# untitled.net
KiCad netlist of a schematic drawn in EAGLE
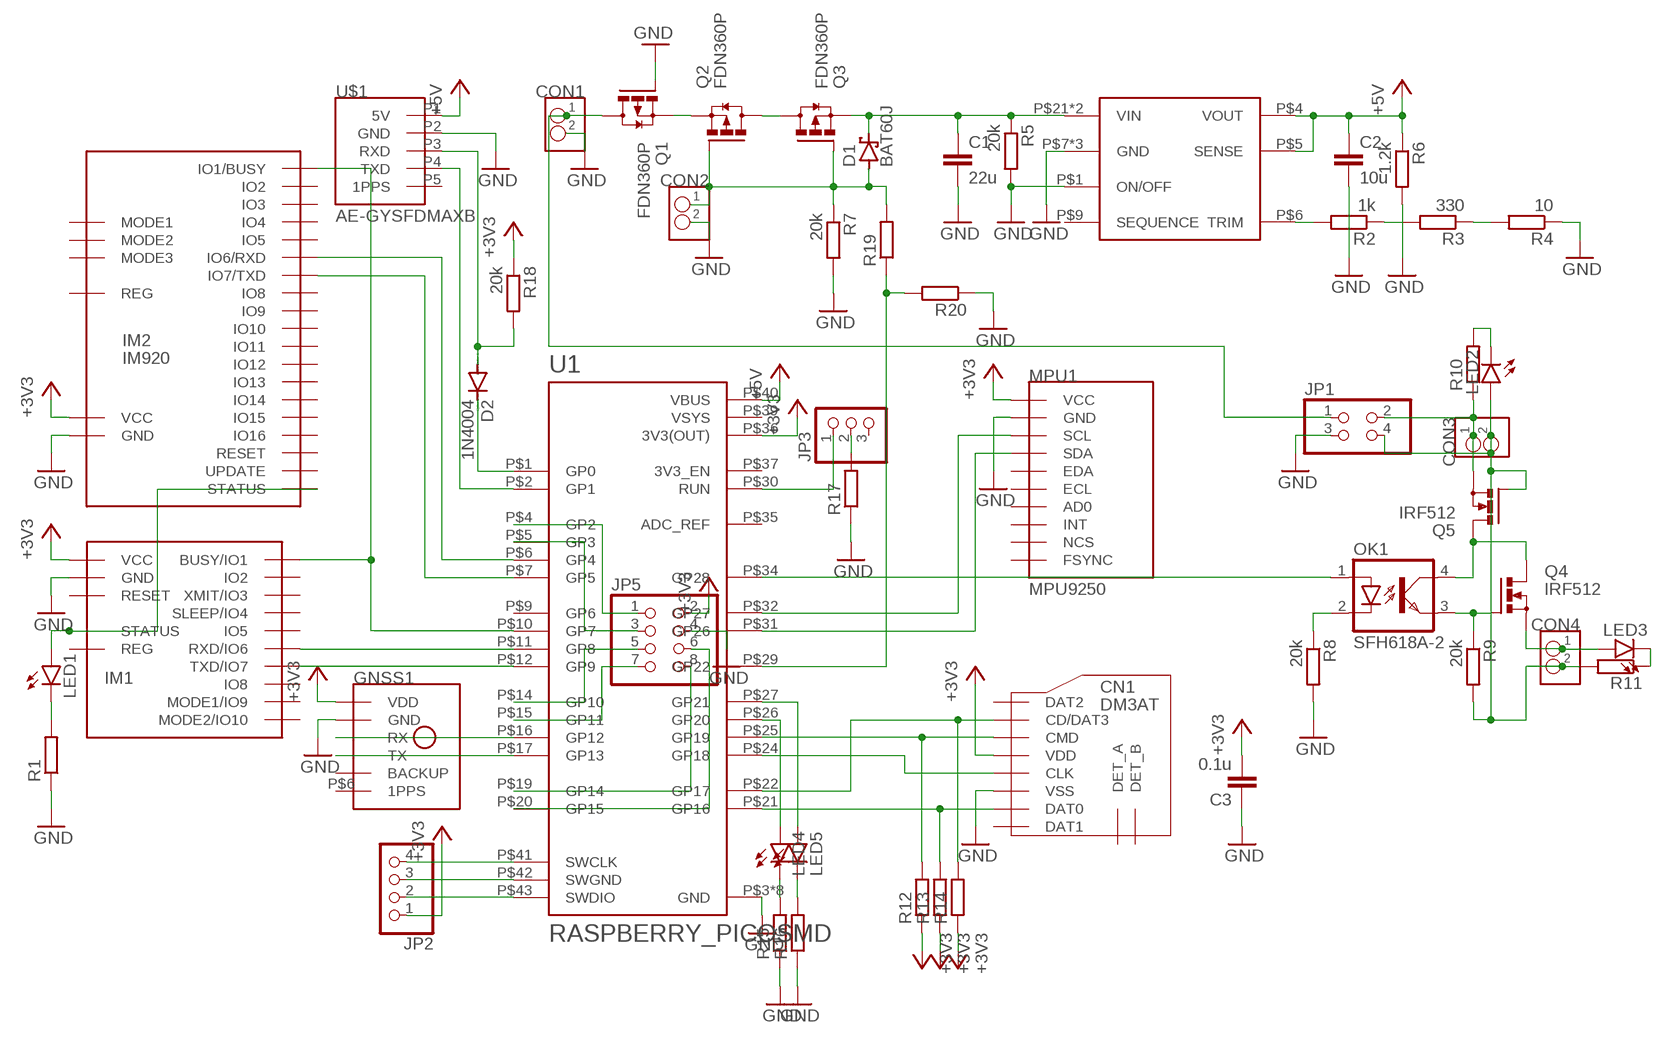
[diagram p0: schematic, sheet 1]

(export (version "E")
  (design (tool "Eeschema 10.0.6"))
  (components
    (comp (ref "C1")
      (value "22u")
      (footprint "eagle-import:C0805")
      (libsource (lib "eagle-import") (part "C-EUC0805"))
    )
    (comp (ref "C2")
      (value "10u")
      (footprint "eagle-import:C0805")
      (libsource (lib "eagle-import") (part "C-EUC0805"))
    )
    (comp (ref "C3")
      (value "0.1u")
      (footprint "eagle-import:C0805")
      (libsource (lib "eagle-import") (part "C-EUC0805"))
    )
    (comp (ref "CN1")
      (value "DM3AT")
      (footprint "eagle-import:DM3AT")
      (libsource (lib "eagle-import") (part "DM3AT"))
    )
    (comp (ref "CON1")
      (value "B2B-XH-A")
      (footprint "eagle-import:B2B-XH-A")
      (libsource (lib "eagle-import") (part "B2B-XH-A"))
    )
    (comp (ref "CON2")
      (value "B2B-XH-A")
      (footprint "eagle-import:B2B-XH-A")
      (libsource (lib "eagle-import") (part "B2B-XH-A"))
    )
    (comp (ref "CON3")
      (value "B2B-XH-A")
      (footprint "eagle-import:B2B-XH-A")
      (libsource (lib "eagle-import") (part "B2B-XH-A"))
    )
    (comp (ref "CON4")
      (value "B2B-XH-A")
      (footprint "eagle-import:B2B-XH-A")
      (libsource (lib "eagle-import") (part "B2B-XH-A"))
    )
    (comp (ref "D1")
      (value "BAT60J")
      (footprint "eagle-import:SOD323_ST")
      (libsource (lib "eagle-import") (part "BAT60J"))
    )
    (comp (ref "D2")
      (value "1N4004")
      (footprint "eagle-import:DO41-10")
      (libsource (lib "eagle-import") (part "1N4004"))
    )
    (comp (ref "GNSS1")
      (value "GYSFDMAXB")
      (footprint "eagle-import:GYSFDMAXB")
      (libsource (lib "eagle-import") (part "GYSFDMAXB"))
    )
    (comp (ref "I1")
      (value "ＯＫＬ-Ｔ/３-Ｗ５Ｎ-Ｃ")
      (footprint "eagle-import:ＯＫＬ-Ｔ_３-Ｗ５Ｎ-Ｃ")
      (libsource (lib "eagle-import") (part "ＯＫＬ-Ｔ/３-Ｗ５Ｎ-Ｃ"))
    )
    (comp (ref "IM1")
      (value "IM920C")
      (footprint "eagle-import:IM920C")
      (libsource (lib "eagle-import") (part "IM920C"))
    )
    (comp (ref "IM2")
      (value "IM920")
      (footprint "eagle-import:IM920")
      (libsource (lib "eagle-import") (part "IM920"))
    )
    (comp (ref "JP1")
      (value "PINHD-2X2")
      (footprint "eagle-import:2X02")
      (libsource (lib "eagle-import") (part "PINHD-2X2"))
    )
    (comp (ref "JP2")
      (value "PINHD-1X4")
      (footprint "eagle-import:1X04")
      (libsource (lib "eagle-import") (part "PINHD-1X4"))
    )
    (comp (ref "JP3")
      (value "PINHD-1X3")
      (footprint "eagle-import:1X03")
      (libsource (lib "eagle-import") (part "PINHD-1X3"))
    )
    (comp (ref "JP5")
      (value "PINHD-2X4")
      (footprint "eagle-import:2X04")
      (libsource (lib "eagle-import") (part "PINHD-2X4"))
    )
    (comp (ref "LED1")
      (value "LEDCHIP-LED0805")
      (footprint "eagle-import:CHIP-LED0805")
      (libsource (lib "eagle-import") (part "LEDCHIP-LED0805"))
    )
    (comp (ref "LED2")
      (value "LEDCHIP-LED0805")
      (footprint "eagle-import:CHIP-LED0805")
      (libsource (lib "eagle-import") (part "LEDCHIP-LED0805"))
    )
    (comp (ref "LED3")
      (value "LEDCHIP-LED0805")
      (footprint "eagle-import:CHIP-LED0805")
      (libsource (lib "eagle-import") (part "LEDCHIP-LED0805"))
    )
    (comp (ref "LED4")
      (value "LEDCHIP-LED0805")
      (footprint "eagle-import:CHIP-LED0805")
      (libsource (lib "eagle-import") (part "LEDCHIP-LED0805"))
    )
    (comp (ref "LED5")
      (value "LEDCHIP-LED0805")
      (footprint "eagle-import:CHIP-LED0805")
      (libsource (lib "eagle-import") (part "LEDCHIP-LED0805"))
    )
    (comp (ref "MPU1")
      (value "MPU9250")
      (footprint "eagle-import:GY-9250")
      (libsource (lib "eagle-import") (part "MPU9250"))
    )
    (comp (ref "OK1")
      (value "SFH618A-2")
      (footprint "eagle-import:DIP4")
      (fields (field (name "MF") "VISHAY/TELEFUNKEN"))
      (libsource (lib "eagle-import") (part "SFH618?A-2"))
    )
    (comp (ref "Q1")
      (value "FDN360P")
      (footprint "eagle-import:SUPER-SOT3")
      (libsource (lib "eagle-import") (part "FDN360P"))
    )
    (comp (ref "Q2")
      (value "FDN360P")
      (footprint "eagle-import:SUPER-SOT3")
      (libsource (lib "eagle-import") (part "FDN360P"))
    )
    (comp (ref "Q3")
      (value "FDN360P")
      (footprint "eagle-import:SUPER-SOT3")
      (libsource (lib "eagle-import") (part "FDN360P"))
    )
    (comp (ref "Q4")
      (value "IRF512")
      (footprint "eagle-import:TO220BV")
      (libsource (lib "eagle-import") (part "IRF512"))
    )
    (comp (ref "Q5")
      (value "IRF512")
      (footprint "eagle-import:TO220BV")
      (libsource (lib "eagle-import") (part "IRF512"))
    )
    (comp (ref "R1")
      (value "R-EU_R0603")
      (footprint "eagle-import:R0603")
      (libsource (lib "eagle-import") (part "R-EU_R0603"))
    )
    (comp (ref "R2")
      (value "1k")
      (footprint "eagle-import:R0603")
      (libsource (lib "eagle-import") (part "R-EU_R0603"))
    )
    (comp (ref "R3")
      (value "330")
      (footprint "eagle-import:R0603")
      (libsource (lib "eagle-import") (part "R-EU_R0603"))
    )
    (comp (ref "R4")
      (value "10")
      (footprint "eagle-import:R0603")
      (libsource (lib "eagle-import") (part "R-EU_R0603"))
    )
    (comp (ref "R5")
      (value "20k")
      (footprint "eagle-import:R0603")
      (libsource (lib "eagle-import") (part "R-EU_R0603"))
    )
    (comp (ref "R6")
      (value "1.2k")
      (footprint "eagle-import:R0603")
      (libsource (lib "eagle-import") (part "R-EU_R0603"))
    )
    (comp (ref "R7")
      (value "20k")
      (footprint "eagle-import:R0603")
      (libsource (lib "eagle-import") (part "R-EU_R0603"))
    )
    (comp (ref "R8")
      (value "20k")
      (footprint "eagle-import:R0603")
      (libsource (lib "eagle-import") (part "R-EU_R0603"))
    )
    (comp (ref "R9")
      (value "20k")
      (footprint "eagle-import:R0603")
      (libsource (lib "eagle-import") (part "R-EU_R0603"))
    )
    (comp (ref "R10")
      (value "R-EU_R0603")
      (footprint "eagle-import:R0603")
      (libsource (lib "eagle-import") (part "R-EU_R0603"))
    )
    (comp (ref "R11")
      (value "R-EU_R0603")
      (footprint "eagle-import:R0603")
      (libsource (lib "eagle-import") (part "R-EU_R0603"))
    )
    (comp (ref "R12")
      (value "R-EU_R0603")
      (footprint "eagle-import:R0603")
      (libsource (lib "eagle-import") (part "R-EU_R0603"))
    )
    (comp (ref "R13")
      (value "R-EU_R0603")
      (footprint "eagle-import:R0603")
      (libsource (lib "eagle-import") (part "R-EU_R0603"))
    )
    (comp (ref "R14")
      (value "R-EU_R0603")
      (footprint "eagle-import:R0603")
      (libsource (lib "eagle-import") (part "R-EU_R0603"))
    )
    (comp (ref "R15")
      (value "R-EU_R0603")
      (footprint "eagle-import:R0603")
      (libsource (lib "eagle-import") (part "R-EU_R0603"))
    )
    (comp (ref "R16")
      (value "R-EU_R0603")
      (footprint "eagle-import:R0603")
      (libsource (lib "eagle-import") (part "R-EU_R0603"))
    )
    (comp (ref "R17")
      (value "R-EU_R0603")
      (footprint "eagle-import:R0603")
      (libsource (lib "eagle-import") (part "R-EU_R0603"))
    )
    (comp (ref "R18")
      (value "20k")
      (footprint "eagle-import:R0603")
      (libsource (lib "eagle-import") (part "R-EU_R0603"))
    )
    (comp (ref "R19")
      (value "R-EU_R0603")
      (footprint "eagle-import:R0603")
      (libsource (lib "eagle-import") (part "R-EU_R0603"))
    )
    (comp (ref "R20")
      (value "R-EU_R0603")
      (footprint "eagle-import:R0603")
      (libsource (lib "eagle-import") (part "R-EU_R0603"))
    )
    (comp (ref "U$1")
      (value "AE-GYSFDMAXB")
      (footprint "eagle-import:AE-GYSFDMAXB")
      (libsource (lib "eagle-import") (part "AE-GYSFDMAXB"))
    )
    (comp (ref "U1")
      (value "RASPBERRY_PICOSMD")
      (footprint "eagle-import:PICO-PKG-SMD")
      (libsource (lib "eagle-import") (part "RASPBERRY_PICOSMD"))
    )
  )
  (nets
    (net (code "1") (name "+3V3") (class "Default")
      (node (ref "C3") (pin "2") (pinfunction "2_2") (pintype "passive"))
      (node (ref "CN1") (pin "VDD") (pinfunction "VDD_VDD") (pintype "bidirectional"))
      (node (ref "GNSS1") (pin "P$16") (pinfunction "VDD_P$16") (pintype "bidirectional"))
      (node (ref "IM1") (pin "$P17") (pinfunction "VCC_$P17") (pintype "bidirectional"))
      (node (ref "IM2") (pin "IO23") (pinfunction "VCC_IO23") (pintype "bidirectional"))
      (node (ref "JP2") (pin "1") (pinfunction "1_1") (pintype "passive"))
      (node (ref "JP5") (pin "2") (pinfunction "2_2") (pintype "passive"))
      (node (ref "MPU1") (pin "P1") (pinfunction "VCC_P1") (pintype "bidirectional"))
      (node (ref "R12") (pin "1") (pinfunction "1_1") (pintype "passive"))
      (node (ref "R13") (pin "1") (pinfunction "1_1") (pintype "passive"))
      (node (ref "R14") (pin "1") (pinfunction "1_1") (pintype "passive"))
      (node (ref "R18") (pin "1") (pinfunction "1_1") (pintype "passive"))
      (node (ref "U1") (pin "P$36") (pinfunction "3V3(OUT)_P$36") (pintype "power_in"))
    )
    (net (code "2") (name "+5V") (class "Default")
      (node (ref "C2") (pin "1") (pinfunction "1_1") (pintype "passive"))
      (node (ref "I1") (pin "P$4") (pinfunction "VOUT_P$4") (pintype "bidirectional"))
      (node (ref "I1") (pin "P$5") (pinfunction "SENSE_P$5") (pintype "bidirectional"))
      (node (ref "R6") (pin "1") (pinfunction "1_1") (pintype "passive"))
      (node (ref "U$1") (pin "P1") (pinfunction "5V_P1") (pintype "bidirectional"))
      (node (ref "U1") (pin "P$40") (pinfunction "VBUS_P$40") (pintype "power_in"))
    )
    (net (code "3") (name "/VSYS") (class "Default")
      (node (ref "U1") (pin "P$39") (pinfunction "VSYS_P$39") (pintype "power_in"))
    )
    (net (code "4") (name "GND") (class "Default")
      (node (ref "C1") (pin "2") (pinfunction "2_2") (pintype "passive"))
      (node (ref "C2") (pin "2") (pinfunction "2_2") (pintype "passive"))
      (node (ref "C3") (pin "1") (pinfunction "1_1") (pintype "passive"))
      (node (ref "CN1") (pin "VSS") (pinfunction "VSS_VSS") (pintype "bidirectional"))
      (node (ref "CON1") (pin "P$2") (pinfunction "2_P$2") (pintype "bidirectional"))
      (node (ref "CON2") (pin "P$2") (pinfunction "2_P$2") (pintype "bidirectional"))
      (node (ref "GNSS1") (pin "P$1") (pinfunction "GND_P$1") (pintype "bidirectional"))
      (node (ref "GNSS1") (pin "P$10") (pinfunction "GND_P$10") (pintype "bidirectional"))
      (node (ref "GNSS1") (pin "P$12") (pinfunction "GND_P$12") (pintype "bidirectional"))
      (node (ref "GNSS1") (pin "P$19") (pinfunction "GND_P$19") (pintype "bidirectional"))
      (node (ref "GNSS1") (pin "P$2") (pinfunction "GND_P$2") (pintype "bidirectional"))
      (node (ref "GNSS1") (pin "P$20") (pinfunction "GND_P$20") (pintype "bidirectional"))
      (node (ref "GNSS1") (pin "P$7") (pinfunction "GND_P$7") (pintype "bidirectional"))
      (node (ref "I1") (pin "P$1") (pinfunction "ON/OFF_P$1") (pintype "bidirectional"))
      (node (ref "I1") (pin "P$31") (pinfunction "GND_P$31") (pintype "bidirectional"))
      (node (ref "I1") (pin "P$32") (pinfunction "GND_P$32") (pintype "bidirectional"))
      (node (ref "I1") (pin "P$7") (pinfunction "GND_P$7") (pintype "bidirectional"))
      (node (ref "IM1") (pin "$P18") (pinfunction "GND_$P18") (pintype "bidirectional"))
      (node (ref "IM2") (pin "IO24") (pinfunction "GND_IO24") (pintype "bidirectional"))
      (node (ref "JP1") (pin "3") (pinfunction "3_3") (pintype "passive"))
      (node (ref "JP5") (pin "4") (pinfunction "4_4") (pintype "passive"))
      (node (ref "MPU1") (pin "P2") (pinfunction "GND_P2") (pintype "bidirectional"))
      (node (ref "Q1") (pin "1") (pinfunction "G_1") (pintype "passive"))
      (node (ref "R1") (pin "1") (pinfunction "1_1") (pintype "passive"))
      (node (ref "R15") (pin "1") (pinfunction "1_1") (pintype "passive"))
      (node (ref "R16") (pin "1") (pinfunction "1_1") (pintype "passive"))
      (node (ref "R17") (pin "1") (pinfunction "1_1") (pintype "passive"))
      (node (ref "R20") (pin "1") (pinfunction "1_1") (pintype "passive"))
      (node (ref "R4") (pin "1") (pinfunction "1_1") (pintype "passive"))
      (node (ref "R5") (pin "2") (pinfunction "2_2") (pintype "passive"))
      (node (ref "R6") (pin "2") (pinfunction "2_2") (pintype "passive"))
      (node (ref "R7") (pin "2") (pinfunction "2_2") (pintype "passive"))
      (node (ref "R8") (pin "2") (pinfunction "2_2") (pintype "passive"))
      (node (ref "U$1") (pin "P2") (pinfunction "GND_P2") (pintype "bidirectional"))
      (node (ref "U1") (pin "P$13") (pinfunction "GND_P$13") (pintype "power_in"))
      (node (ref "U1") (pin "P$18") (pinfunction "GND_P$18") (pintype "power_in"))
      (node (ref "U1") (pin "P$23") (pinfunction "GND_P$23") (pintype "power_in"))
      (node (ref "U1") (pin "P$28") (pinfunction "GND_P$28") (pintype "power_in"))
      (node (ref "U1") (pin "P$3") (pinfunction "GND_P$3") (pintype "power_in"))
      (node (ref "U1") (pin "P$33") (pinfunction "GND_P$33") (pintype "power_in"))
      (node (ref "U1") (pin "P$38") (pinfunction "GND_P$38") (pintype "power_in"))
      (node (ref "U1") (pin "P$8") (pinfunction "GND_P$8") (pintype "power_in"))
    )
    (net (code "5") (name "Net-(CON1-1)") (class "Default")
      (node (ref "CON1") (pin "P$1") (pinfunction "1_P$1") (pintype "bidirectional"))
      (node (ref "JP1") (pin "1") (pinfunction "1_1") (pintype "passive"))
      (node (ref "Q1") (pin "3") (pinfunction "D_3") (pintype "passive"))
    )
    (net (code "6") (name "Net-(CON2-1)") (class "Default")
      (node (ref "CON2") (pin "P$1") (pinfunction "1_P$1") (pintype "bidirectional"))
      (node (ref "D1") (pin "A") (pinfunction "A_A") (pintype "passive"))
      (node (ref "Q2") (pin "1") (pinfunction "G_1") (pintype "passive"))
      (node (ref "Q3") (pin "1") (pinfunction "G_1") (pintype "passive"))
      (node (ref "R19") (pin "2") (pinfunction "2_2") (pintype "passive"))
      (node (ref "R7") (pin "1") (pinfunction "1_1") (pintype "passive"))
    )
    (net (code "7") (name "Net-(CON3-1)") (class "Default")
      (node (ref "CON3") (pin "P$1") (pinfunction "1_P$1") (pintype "bidirectional"))
      (node (ref "JP1") (pin "2") (pinfunction "2_2") (pintype "passive"))
      (node (ref "Q5") (pin "S") (pinfunction "S_S") (pintype "passive"))
      (node (ref "R10") (pin "1") (pinfunction "1_1") (pintype "passive"))
    )
    (net (code "8") (name "Net-(CON3-2)") (class "Default")
      (node (ref "CON3") (pin "P$2") (pinfunction "2_P$2") (pintype "bidirectional"))
      (node (ref "CON4") (pin "P$2") (pinfunction "2_P$2") (pintype "bidirectional"))
      (node (ref "JP1") (pin "4") (pinfunction "4_4") (pintype "passive"))
      (node (ref "LED2") (pin "A") (pinfunction "A_A") (pintype "passive"))
      (node (ref "Q5") (pin "G") (pinfunction "G_G") (pintype "passive"))
      (node (ref "R11") (pin "2") (pinfunction "2_2") (pintype "passive"))
      (node (ref "R9") (pin "2") (pinfunction "2_2") (pintype "passive"))
    )
    (net (code "9") (name "Net-(CON4-1)") (class "Default")
      (node (ref "CON4") (pin "P$1") (pinfunction "1_P$1") (pintype "bidirectional"))
      (node (ref "LED3") (pin "A") (pinfunction "A_A") (pintype "passive"))
      (node (ref "Q4") (pin "S") (pinfunction "S_S") (pintype "passive"))
    )
    (net (code "10") (name "Net-(GNSS1-RX)") (class "Default")
      (node (ref "GNSS1") (pin "P$3") (pinfunction "RX_P$3") (pintype "bidirectional"))
      (node (ref "U1") (pin "P$16") (pinfunction "GP12_P$16") (pintype "bidirectional"))
    )
    (net (code "11") (name "Net-(GNSS1-TX)") (class "Default")
      (node (ref "GNSS1") (pin "P$5") (pinfunction "TX_P$5") (pintype "bidirectional"))
      (node (ref "U1") (pin "P$17") (pinfunction "GP13_P$17") (pintype "bidirectional"))
    )
    (net (code "12") (name "Net-(I1-TRIM)") (class "Default")
      (node (ref "I1") (pin "P$6") (pinfunction "TRIM_P$6") (pintype "bidirectional"))
      (node (ref "R2") (pin "2") (pinfunction "2_2") (pintype "passive"))
    )
    (net (code "13") (name "Net-(IM1-BUSY{slash}IO1)") (class "Default")
      (node (ref "IM1") (pin "$P1") (pinfunction "BUSY/IO1_$P1") (pintype "bidirectional"))
      (node (ref "IM2") (pin "IO1") (pinfunction "IO1/BUSY_IO1") (pintype "bidirectional"))
      (node (ref "U1") (pin "P$10") (pinfunction "GP7_P$10") (pintype "bidirectional"))
    )
    (net (code "14") (name "Net-(IM1-RXD{slash}IO6)") (class "Default")
      (node (ref "IM1") (pin "$P6") (pinfunction "RXD/IO6_$P6") (pintype "bidirectional"))
      (node (ref "U1") (pin "P$11") (pinfunction "GP8_P$11") (pintype "bidirectional"))
    )
    (net (code "15") (name "Net-(IM1-STATUS)") (class "Default")
      (node (ref "IM1") (pin "$P15") (pinfunction "STATUS_$P15") (pintype "bidirectional"))
      (node (ref "IM2") (pin "IO21") (pinfunction "STATUS_IO21") (pintype "bidirectional"))
      (node (ref "LED1") (pin "A") (pinfunction "A_A") (pintype "passive"))
    )
    (net (code "16") (name "Net-(IM1-TXD{slash}IO7)") (class "Default")
      (node (ref "IM1") (pin "$P7") (pinfunction "TXD/IO7_$P7") (pintype "bidirectional"))
      (node (ref "U1") (pin "P$12") (pinfunction "GP9_P$12") (pintype "bidirectional"))
    )
    (net (code "17") (name "Net-(IM2-IO6{slash}RXD)") (class "Default")
      (node (ref "IM2") (pin "IO6") (pinfunction "IO6/RXD_IO6") (pintype "bidirectional"))
      (node (ref "U1") (pin "P$6") (pinfunction "GP4_P$6") (pintype "bidirectional"))
    )
    (net (code "18") (name "Net-(IM2-IO7{slash}TXD)") (class "Default")
      (node (ref "IM2") (pin "IO7") (pinfunction "IO7/TXD_IO7") (pintype "bidirectional"))
      (node (ref "U1") (pin "P$7") (pinfunction "GP5_P$7") (pintype "bidirectional"))
    )
    (net (code "19") (name "Net-(JP3-Pad2)") (class "Default")
      (node (ref "JP3") (pin "2") (pinfunction "2_2") (pintype "passive"))
      (node (ref "R17") (pin "2") (pinfunction "2_2") (pintype "passive"))
    )
    (net (code "20") (name "Net-(LED1-PadC)") (class "Default")
      (node (ref "LED1") (pin "C") (pinfunction "C_C") (pintype "passive"))
      (node (ref "R1") (pin "2") (pinfunction "2_2") (pintype "passive"))
    )
    (net (code "21") (name "Net-(LED2-PadC)") (class "Default")
      (node (ref "LED2") (pin "C") (pinfunction "C_C") (pintype "passive"))
      (node (ref "R10") (pin "2") (pinfunction "2_2") (pintype "passive"))
    )
    (net (code "22") (name "Net-(LED3-PadC)") (class "Default")
      (node (ref "LED3") (pin "C") (pinfunction "C_C") (pintype "passive"))
      (node (ref "R11") (pin "1") (pinfunction "1_1") (pintype "passive"))
    )
    (net (code "23") (name "Net-(LED4-PadC)") (class "Default")
      (node (ref "LED4") (pin "C") (pinfunction "C_C") (pintype "passive"))
      (node (ref "R15") (pin "2") (pinfunction "2_2") (pintype "passive"))
    )
    (net (code "24") (name "Net-(LED5-PadC)") (class "Default")
      (node (ref "LED5") (pin "C") (pinfunction "C_C") (pintype "passive"))
      (node (ref "R16") (pin "2") (pinfunction "2_2") (pintype "passive"))
    )
    (net (code "25") (name "Net-(MPU1-SCL)") (class "Default")
      (node (ref "MPU1") (pin "P3") (pinfunction "SCL_P3") (pintype "bidirectional"))
      (node (ref "U1") (pin "P$32") (pinfunction "GP27_P$32") (pintype "bidirectional"))
    )
    (net (code "26") (name "Net-(MPU1-SDA)") (class "Default")
      (node (ref "MPU1") (pin "P4") (pinfunction "SDA_P4") (pintype "bidirectional"))
      (node (ref "U1") (pin "P$31") (pinfunction "GP26_P$31") (pintype "bidirectional"))
    )
    (net (code "27") (name "Net-(OK1-A)") (class "Default")
      (node (ref "OK1") (pin "1") (pinfunction "A_1") (pintype "passive"))
      (node (ref "U1") (pin "P$34") (pinfunction "GP28_P$34") (pintype "bidirectional"))
    )
    (net (code "28") (name "Net-(OK1-C)") (class "Default")
      (node (ref "OK1") (pin "2") (pinfunction "C_2") (pintype "passive"))
      (node (ref "R8") (pin "1") (pinfunction "1_1") (pintype "passive"))
    )
    (net (code "29") (name "Net-(OK1-COL)") (class "Default")
      (node (ref "OK1") (pin "4") (pinfunction "COL_4") (pintype "passive"))
      (node (ref "Q4") (pin "D") (pinfunction "D_D") (pintype "passive"))
      (node (ref "Q5") (pin "D") (pinfunction "D_D") (pintype "passive"))
    )
    (net (code "30") (name "Net-(OK1-EMIT)") (class "Default")
      (node (ref "OK1") (pin "3") (pinfunction "EMIT_3") (pintype "passive"))
      (node (ref "Q4") (pin "G") (pinfunction "G_G") (pintype "passive"))
      (node (ref "R9") (pin "1") (pinfunction "1_1") (pintype "passive"))
    )
    (net (code "31") (name "Net-(Q1-S)") (class "Default")
      (node (ref "Q1") (pin "2") (pinfunction "S_2") (pintype "passive"))
      (node (ref "Q2") (pin "2") (pinfunction "S_2") (pintype "passive"))
    )
    (net (code "32") (name "Net-(Q2-D)") (class "Default")
      (node (ref "Q2") (pin "3") (pinfunction "D_3") (pintype "passive"))
      (node (ref "Q3") (pin "3") (pinfunction "D_3") (pintype "passive"))
    )
    (net (code "33") (name "Net-(Q3-S)") (class "Default")
      (node (ref "C1") (pin "1") (pinfunction "1_1") (pintype "passive"))
      (node (ref "D1") (pin "C") (pinfunction "C_C") (pintype "passive"))
      (node (ref "I1") (pin "P$21") (pinfunction "VIN_P$21") (pintype "bidirectional"))
      (node (ref "I1") (pin "P$22") (pinfunction "VIN_P$22") (pintype "bidirectional"))
      (node (ref "Q3") (pin "2") (pinfunction "S_2") (pintype "passive"))
      (node (ref "R5") (pin "1") (pinfunction "1_1") (pintype "passive"))
    )
    (net (code "34") (name "Net-(R2-Pad1)") (class "Default")
      (node (ref "R2") (pin "1") (pinfunction "1_1") (pintype "passive"))
      (node (ref "R3") (pin "2") (pinfunction "2_2") (pintype "passive"))
    )
    (net (code "35") (name "Net-(R3-Pad1)") (class "Default")
      (node (ref "R3") (pin "1") (pinfunction "1_1") (pintype "passive"))
      (node (ref "R4") (pin "2") (pinfunction "2_2") (pintype "passive"))
    )
    (net (code "36") (name "Net-(U$1-RXD)") (class "Default")
      (node (ref "D2") (pin "A") (pinfunction "A_A") (pintype "passive"))
      (node (ref "R18") (pin "2") (pinfunction "2_2") (pintype "passive"))
      (node (ref "U$1") (pin "P3") (pinfunction "RXD_P3") (pintype "bidirectional"))
    )
    (net (code "37") (name "Net-(U$1-TXD)") (class "Default")
      (node (ref "U$1") (pin "P4") (pinfunction "TXD_P4") (pintype "bidirectional"))
      (node (ref "U1") (pin "P$2") (pinfunction "GP1_P$2") (pintype "bidirectional"))
    )
    (net (code "38") (name "Net-(U1-GP0)") (class "Default")
      (node (ref "D2") (pin "C") (pinfunction "C_C") (pintype "passive"))
      (node (ref "U1") (pin "P$1") (pinfunction "GP0_P$1") (pintype "bidirectional"))
    )
    (net (code "39") (name "Net-(U1-GP2)") (class "Default")
      (node (ref "JP5") (pin "1") (pinfunction "1_1") (pintype "passive"))
      (node (ref "U1") (pin "P$4") (pinfunction "GP2_P$4") (pintype "bidirectional"))
    )
    (net (code "40") (name "Net-(U1-GP3)") (class "Default")
      (node (ref "JP5") (pin "3") (pinfunction "3_3") (pintype "passive"))
      (node (ref "U1") (pin "P$5") (pinfunction "GP3_P$5") (pintype "bidirectional"))
    )
    (net (code "41") (name "Net-(U1-GP10)") (class "Default")
      (node (ref "JP5") (pin "5") (pinfunction "5_5") (pintype "passive"))
      (node (ref "U1") (pin "P$14") (pinfunction "GP10_P$14") (pintype "bidirectional"))
    )
    (net (code "42") (name "Net-(U1-GP11)") (class "Default")
      (node (ref "JP5") (pin "7") (pinfunction "7_7") (pintype "passive"))
      (node (ref "U1") (pin "P$15") (pinfunction "GP11_P$15") (pintype "bidirectional"))
    )
    (net (code "43") (name "Net-(U1-GP14)") (class "Default")
      (node (ref "JP5") (pin "8") (pinfunction "8_8") (pintype "passive"))
      (node (ref "U1") (pin "P$19") (pinfunction "GP14_P$19") (pintype "bidirectional"))
    )
    (net (code "44") (name "Net-(U1-GP15)") (class "Default")
      (node (ref "JP5") (pin "6") (pinfunction "6_6") (pintype "passive"))
      (node (ref "U1") (pin "P$20") (pinfunction "GP15_P$20") (pintype "bidirectional"))
    )
    (net (code "45") (name "Net-(U1-GP16)") (class "Default")
      (node (ref "CN1") (pin "DAT0") (pinfunction "DAT0_DAT0") (pintype "bidirectional"))
      (node (ref "R13") (pin "2") (pinfunction "2_2") (pintype "passive"))
      (node (ref "U1") (pin "P$21") (pinfunction "GP16_P$21") (pintype "bidirectional"))
    )
    (net (code "46") (name "Net-(U1-GP17)") (class "Default")
      (node (ref "CN1") (pin "CD/DAT3") (pinfunction "CD/DAT3_CD/DAT3") (pintype "bidirectional"))
      (node (ref "R14") (pin "2") (pinfunction "2_2") (pintype "passive"))
      (node (ref "U1") (pin "P$22") (pinfunction "GP17_P$22") (pintype "bidirectional"))
    )
    (net (code "47") (name "Net-(U1-GP18)") (class "Default")
      (node (ref "CN1") (pin "CLK") (pinfunction "CLK_CLK") (pintype "bidirectional"))
      (node (ref "U1") (pin "P$24") (pinfunction "GP18_P$24") (pintype "bidirectional"))
    )
    (net (code "48") (name "Net-(U1-GP19)") (class "Default")
      (node (ref "CN1") (pin "CMD") (pinfunction "CMD_CMD") (pintype "bidirectional"))
      (node (ref "R12") (pin "2") (pinfunction "2_2") (pintype "passive"))
      (node (ref "U1") (pin "P$25") (pinfunction "GP19_P$25") (pintype "bidirectional"))
    )
    (net (code "49") (name "Net-(U1-GP20)") (class "Default")
      (node (ref "LED4") (pin "A") (pinfunction "A_A") (pintype "passive"))
      (node (ref "U1") (pin "P$26") (pinfunction "GP20_P$26") (pintype "bidirectional"))
    )
    (net (code "50") (name "Net-(U1-GP21)") (class "Default")
      (node (ref "LED5") (pin "A") (pinfunction "A_A") (pintype "passive"))
      (node (ref "U1") (pin "P$27") (pinfunction "GP21_P$27") (pintype "bidirectional"))
    )
    (net (code "51") (name "Net-(U1-GP22)") (class "Default")
      (node (ref "R19") (pin "1") (pinfunction "1_1") (pintype "passive"))
      (node (ref "R20") (pin "2") (pinfunction "2_2") (pintype "passive"))
      (node (ref "U1") (pin "P$29") (pinfunction "GP22_P$29") (pintype "bidirectional"))
    )
    (net (code "52") (name "Net-(U1-RUN)") (class "Default")
      (node (ref "JP3") (pin "1") (pinfunction "1_1") (pintype "passive"))
      (node (ref "U1") (pin "P$30") (pinfunction "RUN_P$30") (pintype "input"))
    )
    (net (code "53") (name "Net-(U1-SWCLK)") (class "Default")
      (node (ref "JP2") (pin "4") (pinfunction "4_4") (pintype "passive"))
      (node (ref "U1") (pin "P$41") (pinfunction "SWCLK_P$41") (pintype "input"))
    )
    (net (code "54") (name "Net-(U1-SWDIO)") (class "Default")
      (node (ref "JP2") (pin "2") (pinfunction "2_2") (pintype "passive"))
      (node (ref "U1") (pin "P$43") (pinfunction "SWDIO_P$43") (pintype "bidirectional"))
    )
    (net (code "55") (name "Net-(U1-SWGND)") (class "Default")
      (node (ref "JP2") (pin "3") (pinfunction "3_3") (pintype "passive"))
      (node (ref "U1") (pin "P$42") (pinfunction "SWGND_P$42") (pintype "power_in"))
    )
    (net (code "56") (name "unconnected-(CN1-PadDAT1)") (class "Default")
      (node (ref "CN1") (pin "DAT1") (pinfunction "DAT1_DAT1") (pintype "bidirectional"))
    )
    (net (code "57") (name "unconnected-(CN1-PadDAT2)") (class "Default")
      (node (ref "CN1") (pin "DAT2") (pinfunction "DAT2_DAT2") (pintype "bidirectional"))
    )
    (net (code "58") (name "unconnected-(CN1-PadDET_A)") (class "Default")
      (node (ref "CN1") (pin "DET_A") (pinfunction "DET_A_DET_A") (pintype "bidirectional"))
    )
    (net (code "59") (name "unconnected-(CN1-PadDET_B)") (class "Default")
      (node (ref "CN1") (pin "DET_B") (pinfunction "DET_B_DET_B") (pintype "bidirectional"))
    )
    (net (code "60") (name "unconnected-(GNSS1-1PPS-PadP$6)") (class "Default")
      (node (ref "GNSS1") (pin "P$6") (pinfunction "1PPS_P$6") (pintype "bidirectional"))
    )
    (net (code "61") (name "unconnected-(GNSS1-BACKUP-PadP$14)") (class "Default")
      (node (ref "GNSS1") (pin "P$14") (pinfunction "BACKUP_P$14") (pintype "bidirectional"))
    )
    (net (code "62") (name "unconnected-(I1-SEQUENCE-PadP$9)") (class "Default")
      (node (ref "I1") (pin "P$9") (pinfunction "SEQUENCE_P$9") (pintype "bidirectional"))
    )
    (net (code "63") (name "unconnected-(IM1-IO2-Pad$P2)") (class "Default")
      (node (ref "IM1") (pin "$P2") (pinfunction "IO2_$P2") (pintype "bidirectional"))
    )
    (net (code "64") (name "unconnected-(IM1-IO5-Pad$P5)") (class "Default")
      (node (ref "IM1") (pin "$P5") (pinfunction "IO5_$P5") (pintype "bidirectional"))
    )
    (net (code "65") (name "unconnected-(IM1-IO8-Pad$P8)") (class "Default")
      (node (ref "IM1") (pin "$P8") (pinfunction "IO8_$P8") (pintype "bidirectional"))
    )
    (net (code "66") (name "unconnected-(IM1-MODE1{slash}IO9-Pad$P9)") (class "Default")
      (node (ref "IM1") (pin "$P9") (pinfunction "MODE1/IO9_$P9") (pintype "bidirectional"))
    )
    (net (code "67") (name "unconnected-(IM1-MODE2{slash}IO10-Pad$P10)") (class "Default")
      (node (ref "IM1") (pin "$P10") (pinfunction "MODE2/IO10_$P10") (pintype "bidirectional"))
    )
    (net (code "68") (name "unconnected-(IM1-REG-Pad$P16)") (class "Default")
      (node (ref "IM1") (pin "$P16") (pinfunction "REG_$P16") (pintype "bidirectional"))
    )
    (net (code "69") (name "unconnected-(IM1-RESET-Pad$P19)") (class "Default")
      (node (ref "IM1") (pin "$P19") (pinfunction "RESET_$P19") (pintype "bidirectional"))
    )
    (net (code "70") (name "unconnected-(IM1-SLEEP{slash}IO4-Pad$P4)") (class "Default")
      (node (ref "IM1") (pin "$P4") (pinfunction "SLEEP/IO4_$P4") (pintype "bidirectional"))
    )
    (net (code "71") (name "unconnected-(IM1-XMIT{slash}IO3-Pad$P3)") (class "Default")
      (node (ref "IM1") (pin "$P3") (pinfunction "XMIT/IO3_$P3") (pintype "bidirectional"))
    )
    (net (code "72") (name "unconnected-(IM2-MODE1-PadIO17)") (class "Default")
      (node (ref "IM2") (pin "IO17") (pinfunction "MODE1_IO17") (pintype "bidirectional"))
    )
    (net (code "73") (name "unconnected-(IM2-MODE2-PadIO18)") (class "Default")
      (node (ref "IM2") (pin "IO18") (pinfunction "MODE2_IO18") (pintype "bidirectional"))
    )
    (net (code "74") (name "unconnected-(IM2-MODE3-PadIO19)") (class "Default")
      (node (ref "IM2") (pin "IO19") (pinfunction "MODE3_IO19") (pintype "bidirectional"))
    )
    (net (code "75") (name "unconnected-(IM2-PadIO2)") (class "Default")
      (node (ref "IM2") (pin "IO2") (pinfunction "IO2_IO2") (pintype "bidirectional"))
    )
    (net (code "76") (name "unconnected-(IM2-PadIO3)") (class "Default")
      (node (ref "IM2") (pin "IO3") (pinfunction "IO3_IO3") (pintype "bidirectional"))
    )
    (net (code "77") (name "unconnected-(IM2-PadIO4)") (class "Default")
      (node (ref "IM2") (pin "IO4") (pinfunction "IO4_IO4") (pintype "bidirectional"))
    )
    (net (code "78") (name "unconnected-(IM2-PadIO5)") (class "Default")
      (node (ref "IM2") (pin "IO5") (pinfunction "IO5_IO5") (pintype "bidirectional"))
    )
    (net (code "79") (name "unconnected-(IM2-PadIO8)") (class "Default")
      (node (ref "IM2") (pin "IO8") (pinfunction "IO8_IO8") (pintype "bidirectional"))
    )
    (net (code "80") (name "unconnected-(IM2-PadIO9)") (class "Default")
      (node (ref "IM2") (pin "IO9") (pinfunction "IO9_IO9") (pintype "bidirectional"))
    )
    (net (code "81") (name "unconnected-(IM2-PadIO10)") (class "Default")
      (node (ref "IM2") (pin "IO10") (pinfunction "IO10_IO10") (pintype "bidirectional"))
    )
    (net (code "82") (name "unconnected-(IM2-PadIO11)") (class "Default")
      (node (ref "IM2") (pin "IO11") (pinfunction "IO11_IO11") (pintype "bidirectional"))
    )
    (net (code "83") (name "unconnected-(IM2-PadIO12)") (class "Default")
      (node (ref "IM2") (pin "IO12") (pinfunction "IO12_IO12") (pintype "bidirectional"))
    )
    (net (code "84") (name "unconnected-(IM2-PadIO13)") (class "Default")
      (node (ref "IM2") (pin "IO13") (pinfunction "IO13_IO13") (pintype "bidirectional"))
    )
    (net (code "85") (name "unconnected-(IM2-PadIO14)") (class "Default")
      (node (ref "IM2") (pin "IO14") (pinfunction "IO14_IO14") (pintype "bidirectional"))
    )
    (net (code "86") (name "unconnected-(IM2-PadIO15)") (class "Default")
      (node (ref "IM2") (pin "IO15") (pinfunction "IO15_IO15") (pintype "bidirectional"))
    )
    (net (code "87") (name "unconnected-(IM2-PadIO16)") (class "Default")
      (node (ref "IM2") (pin "IO16") (pinfunction "IO16_IO16") (pintype "bidirectional"))
    )
    (net (code "88") (name "unconnected-(IM2-REG-PadIO22)") (class "Default")
      (node (ref "IM2") (pin "IO22") (pinfunction "REG_IO22") (pintype "bidirectional"))
    )
    (net (code "89") (name "unconnected-(IM2-RESET-PadIO25)") (class "Default")
      (node (ref "IM2") (pin "IO25") (pinfunction "RESET_IO25") (pintype "bidirectional"))
    )
    (net (code "90") (name "unconnected-(IM2-UPDATE-PadIO20)") (class "Default")
      (node (ref "IM2") (pin "IO20") (pinfunction "UPDATE_IO20") (pintype "bidirectional"))
    )
    (net (code "91") (name "unconnected-(JP3-Pad3)") (class "Default")
      (node (ref "JP3") (pin "3") (pinfunction "3_3") (pintype "passive"))
    )
    (net (code "92") (name "unconnected-(MPU1-AD0-PadP7)") (class "Default")
      (node (ref "MPU1") (pin "P7") (pinfunction "AD0_P7") (pintype "bidirectional"))
    )
    (net (code "93") (name "unconnected-(MPU1-ECL-PadP6)") (class "Default")
      (node (ref "MPU1") (pin "P6") (pinfunction "ECL_P6") (pintype "bidirectional"))
    )
    (net (code "94") (name "unconnected-(MPU1-EDA-PadP5)") (class "Default")
      (node (ref "MPU1") (pin "P5") (pinfunction "EDA_P5") (pintype "bidirectional"))
    )
    (net (code "95") (name "unconnected-(MPU1-FSYNC-PadP10)") (class "Default")
      (node (ref "MPU1") (pin "P10") (pinfunction "FSYNC_P10") (pintype "bidirectional"))
    )
    (net (code "96") (name "unconnected-(MPU1-INT-PadP8)") (class "Default")
      (node (ref "MPU1") (pin "P8") (pinfunction "INT_P8") (pintype "bidirectional"))
    )
    (net (code "97") (name "unconnected-(MPU1-NCS-PadP9)") (class "Default")
      (node (ref "MPU1") (pin "P9") (pinfunction "NCS_P9") (pintype "bidirectional"))
    )
    (net (code "98") (name "unconnected-(U$1-1PPS-PadP5)") (class "Default")
      (node (ref "U$1") (pin "P5") (pinfunction "1PPS_P5") (pintype "bidirectional"))
    )
    (net (code "99") (name "unconnected-(U1-3V3_EN-PadP$37)") (class "Default")
      (node (ref "U1") (pin "P$37") (pinfunction "3V3_EN_P$37") (pintype "input"))
    )
    (net (code "100") (name "unconnected-(U1-ADC_REF-PadP$35)") (class "Default")
      (node (ref "U1") (pin "P$35") (pinfunction "ADC_REF_P$35") (pintype "input"))
    )
    (net (code "101") (name "unconnected-(U1-GP6-PadP$9)") (class "Default")
      (node (ref "U1") (pin "P$9") (pinfunction "GP6_P$9") (pintype "bidirectional"))
    )
  )
)
